# 1_2.net
KiCad netlist of a schematic drawn in EAGLE
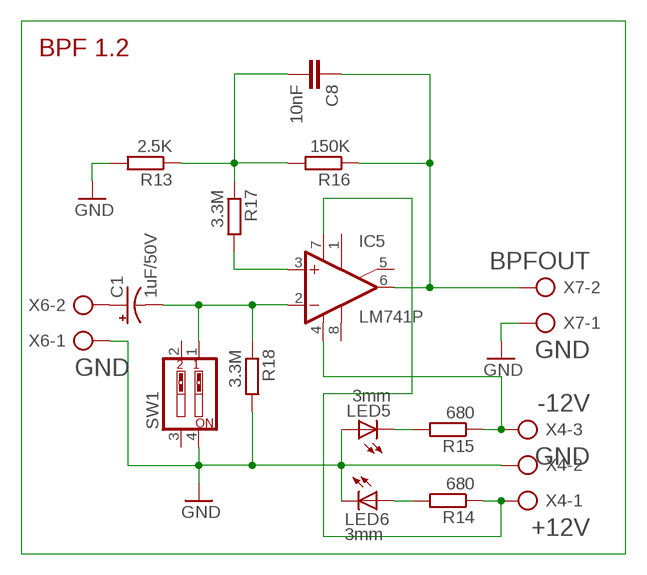
[diagram p0: schematic, sheet 1]

(export (version "E")
  (design (tool "Eeschema 10.0.6"))
  (components
    (comp (ref "C1")
      (value "1uF/50V")
      (footprint "eagle-import:E2,5-6E")
      (libsource (lib "eagle-import") (part "CPOL-USE2,5-6E"))
    )
    (comp (ref "C8")
      (value "10nF")
      (footprint "eagle-import:C050-025X075")
      (libsource (lib "eagle-import") (part "C-EU050-025X075"))
    )
    (comp (ref "IC5")
      (value "LM741P")
      (footprint "eagle-import:DIL08")
      (libsource (lib "eagle-import") (part "741PLM"))
    )
    (comp (ref "LED5")
      (value "3mm")
      (footprint "eagle-import:LED5MM")
      (libsource (lib "eagle-import") (part "LED5MM"))
    )
    (comp (ref "LED6")
      (value "3mm")
      (footprint "eagle-import:LED5MM")
      (libsource (lib "eagle-import") (part "LED5MM"))
    )
    (comp (ref "R13")
      (value "2.5K")
      (footprint "eagle-import:0207_10")
      (libsource (lib "eagle-import") (part "R-EU_0207/10"))
    )
    (comp (ref "R14")
      (value "680")
      (footprint "eagle-import:0207_10")
      (libsource (lib "eagle-import") (part "R-EU_0207/10"))
    )
    (comp (ref "R15")
      (value "680")
      (footprint "eagle-import:0207_10")
      (libsource (lib "eagle-import") (part "R-EU_0207/10"))
    )
    (comp (ref "R16")
      (value "150K")
      (footprint "eagle-import:0207_10")
      (libsource (lib "eagle-import") (part "R-EU_0207/10"))
    )
    (comp (ref "R17")
      (value "3.3M")
      (footprint "eagle-import:0207_10")
      (libsource (lib "eagle-import") (part "R-EU_0207/10"))
    )
    (comp (ref "R18")
      (value "3.3M")
      (footprint "eagle-import:0207_10")
      (libsource (lib "eagle-import") (part "R-EU_0207/10"))
    )
    (comp (ref "SW1")
      (value "SW_DIP-2")
      (footprint "eagle-import:EDG-02")
      (libsource (lib "eagle-import") (part "SW_DIP-2"))
    )
    (comp (ref "X4")
      (value "AK500/3-H")
      (footprint "eagle-import:AK500_3-H")
      (libsource (lib "eagle-import") (part "AK500/3-H"))
    )
    (comp (ref "X6")
      (value "AK500/2-H")
      (footprint "eagle-import:AK500_2-H")
      (libsource (lib "eagle-import") (part "AK500/2-H"))
    )
    (comp (ref "X7")
      (value "AK500/2-H")
      (footprint "eagle-import:AK500_2-H")
      (libsource (lib "eagle-import") (part "AK500/2-H"))
    )
  )
  (nets
    (net (code "1") (name "/+12V") (class "Default")
      (node (ref "IC5") (pin "7") (pinfunction "V+_7") (pintype "power_in"))
      (node (ref "R14") (pin "1") (pinfunction "1_1") (pintype "passive"))
      (node (ref "X4") (pin "1") (pinfunction "KL_1") (pintype "passive"))
    )
    (net (code "2") (name "/-12V") (class "Default")
      (node (ref "IC5") (pin "4") (pinfunction "V-_4") (pintype "power_in"))
      (node (ref "R15") (pin "1") (pinfunction "1_1") (pintype "passive"))
      (node (ref "X4") (pin "3") (pinfunction "KL_3") (pintype "passive"))
    )
    (net (code "3") (name "/BPFOUT") (class "Default")
      (node (ref "C8") (pin "1") (pinfunction "1_1") (pintype "passive"))
      (node (ref "IC5") (pin "6") (pinfunction "OUT_6") (pintype "output"))
      (node (ref "R16") (pin "1") (pinfunction "1_1") (pintype "passive"))
      (node (ref "X7") (pin "2") (pinfunction "KL_2") (pintype "passive"))
    )
    (net (code "4") (name "GND") (class "Default")
      (node (ref "LED5") (pin "A") (pinfunction "A_A") (pintype "passive"))
      (node (ref "LED6") (pin "K") (pinfunction "C_K") (pintype "passive"))
      (node (ref "R13") (pin "2") (pinfunction "2_2") (pintype "passive"))
      (node (ref "R18") (pin "2") (pinfunction "2_2") (pintype "passive"))
      (node (ref "SW1") (pin "4") (pinfunction "4_4") (pintype "passive"))
      (node (ref "X4") (pin "2") (pinfunction "KL_2") (pintype "passive"))
      (node (ref "X6") (pin "1") (pinfunction "KL_1") (pintype "passive"))
      (node (ref "X7") (pin "1") (pinfunction "KL_1") (pintype "passive"))
    )
    (net (code "5") (name "Net-(C8-Pad2)") (class "Default")
      (node (ref "C8") (pin "2") (pinfunction "2_2") (pintype "passive"))
      (node (ref "R13") (pin "1") (pinfunction "1_1") (pintype "passive"))
      (node (ref "R16") (pin "2") (pinfunction "2_2") (pintype "passive"))
      (node (ref "R17") (pin "1") (pinfunction "1_1") (pintype "passive"))
    )
    (net (code "6") (name "Net-(IC5-+IN)") (class "Default")
      (node (ref "IC5") (pin "3") (pinfunction "+IN_3") (pintype "input"))
      (node (ref "R17") (pin "2") (pinfunction "2_2") (pintype "passive"))
    )
    (net (code "7") (name "Net-(IC5--IN)") (class "Default")
      (node (ref "C1") (pin "-") (pinfunction "-_-") (pintype "passive"))
      (node (ref "IC5") (pin "2") (pinfunction "-IN_2") (pintype "input"))
      (node (ref "R18") (pin "1") (pinfunction "1_1") (pintype "passive"))
      (node (ref "SW1") (pin "1") (pinfunction "1_1") (pintype "passive"))
    )
    (net (code "8") (name "Net-(LED5-C)") (class "Default")
      (node (ref "LED5") (pin "K") (pinfunction "C_K") (pintype "passive"))
      (node (ref "R15") (pin "2") (pinfunction "2_2") (pintype "passive"))
    )
    (net (code "9") (name "Net-(LED6-PadA)") (class "Default")
      (node (ref "LED6") (pin "A") (pinfunction "A_A") (pintype "passive"))
      (node (ref "R14") (pin "2") (pinfunction "2_2") (pintype "passive"))
    )
    (net (code "10") (name "Net-(X6B-KL)") (class "Default")
      (node (ref "C1") (pin "+") (pinfunction "+_+") (pintype "passive"))
      (node (ref "X6") (pin "2") (pinfunction "KL_2") (pintype "passive"))
    )
    (net (code "11") (name "unconnected-(IC5-ON1-Pad1)") (class "Default")
      (node (ref "IC5") (pin "1") (pinfunction "ON1_1") (pintype "passive"))
    )
    (net (code "12") (name "unconnected-(IC5-ON2-Pad5)") (class "Default")
      (node (ref "IC5") (pin "5") (pinfunction "ON2_5") (pintype "passive"))
    )
    (net (code "13") (name "unconnected-(IC5-OPT-Pad8)") (class "Default")
      (node (ref "IC5") (pin "8") (pinfunction "OPT_8") (pintype "passive"))
    )
    (net (code "14") (name "unconnected-(SW1-Pad2)") (class "Default")
      (node (ref "SW1") (pin "2") (pinfunction "2_2") (pintype "passive"))
    )
    (net (code "15") (name "unconnected-(SW1-Pad3)") (class "Default")
      (node (ref "SW1") (pin "3") (pinfunction "3_3") (pintype "passive"))
    )
  )
)
